# 51.net
KiCad netlist of a schematic drawn in Altium Designer
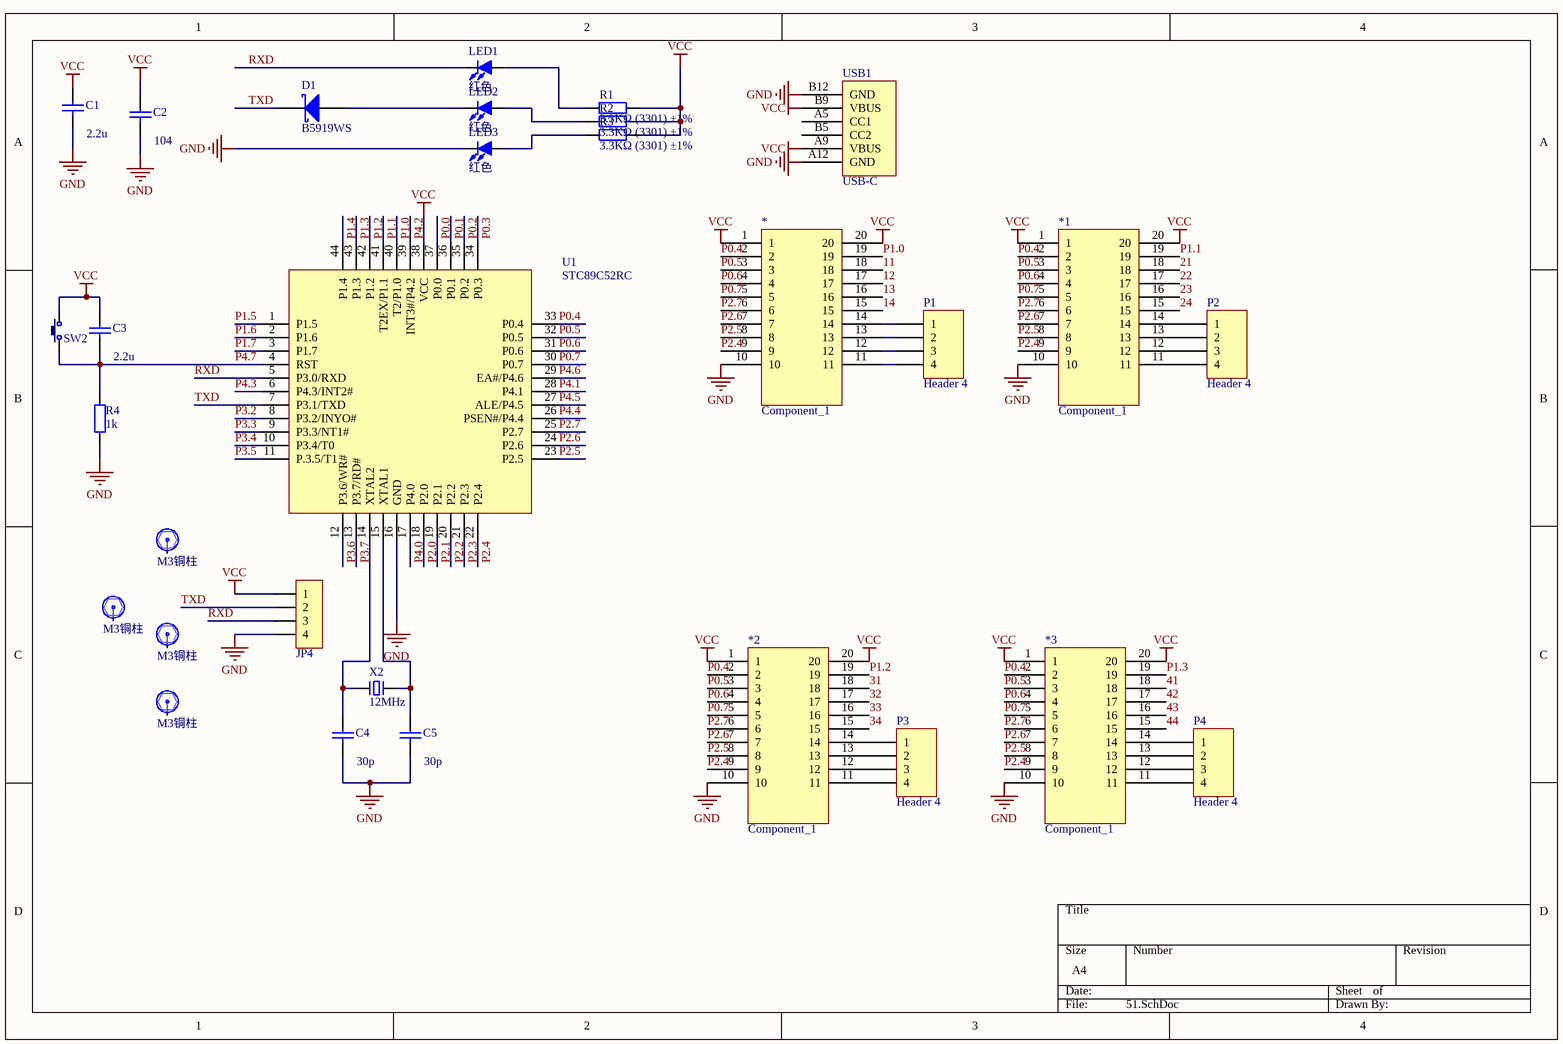
[diagram p0: 51.SchDoc]

(export (version "E")
  (design (tool "Eeschema 10.0.6"))
  (components
    (comp (ref "*")
      (value "Component_1")
      (footprint "SOP20_N")
      (libsource (lib "Schlib1") (part "Component_1"))
    )
    (comp (ref "*1")
      (value "Component_1")
      (footprint "SOP20_N")
      (libsource (lib "Schlib1") (part "Component_1"))
    )
    (comp (ref "*2")
      (value "Component_1")
      (footprint "SOP20_N")
      (libsource (lib "Schlib1") (part "Component_1"))
    )
    (comp (ref "*3")
      (value "Component_1")
      (footprint "SOP20_N")
      (libsource (lib "Schlib1") (part "Component_1"))
    )
    (comp (ref "C1")
      (value "2.2u")
      (footprint "0603_C")
      (description "贴片电容")
      (libsource (lib "Miscellaneous Devices LC") (part "0603 1uF (105) 10% 50V"))
    )
    (comp (ref "C2")
      (value "104")
      (footprint "0603_C")
      (description "贴片电容")
      (libsource (lib "Miscellaneous Devices LC") (part "0603 1uF (105) 10% 50V"))
    )
    (comp (ref "C3")
      (value "2.2u")
      (footprint "0603_C")
      (description "贴片电容")
      (libsource (lib "Miscellaneous Devices LC") (part "0603 1uF (105) 10% 50V"))
    )
    (comp (ref "C4")
      (value "30p")
      (footprint "0603_C")
      (description "贴片电容")
      (libsource (lib "Miscellaneous Devices LC") (part "0603 1uF (105) 10% 50V"))
    )
    (comp (ref "C5")
      (value "30p")
      (footprint "0603_C")
      (description "贴片电容")
      (libsource (lib "Miscellaneous Devices LC") (part "0603 1uF (105) 10% 50V"))
    )
    (comp (ref "D1")
      (value "B5919WS")
      (footprint "SMA")
      (description "肖特基二极管")
      (libsource (lib "0.2 - 二极管-整流桥") (part "1N5819"))
    )
    (comp (ref "JP4")
      (value "HDR-1X4")
      (footprint "HDR2.54-LI-4P")
      (description "4P接插件")
      (fields (field (name "版权归属") "封装库来自淘宝 ID：黄晶宝石"))
      (libsource (lib "5.4 - 接插件-脚距2.54 (100mil) ") (part "Header 4"))
    )
    (comp (ref "LED1")
      (value "红色")
      (footprint "LED 0603R")
      (description "贴片LED")
      (fields (field (name "版权归属") "封装库来自淘宝 ID：黄晶宝石"))
      (libsource (lib "0.3 - LED发光二极管") (part "LED-SMD"))
    )
    (comp (ref "LED2")
      (value "红色")
      (footprint "LED 0603R")
      (description "贴片LED")
      (fields (field (name "版权归属") "封装库来自淘宝 ID：黄晶宝石"))
      (libsource (lib "0.3 - LED发光二极管") (part "LED-SMD"))
    )
    (comp (ref "LED3")
      (value "红色")
      (footprint "LED 0603R")
      (description "贴片LED")
      (fields (field (name "版权归属") "封装库来自淘宝 ID：黄晶宝石"))
      (libsource (lib "0.3 - LED发光二极管") (part "LED-SMD"))
    )
    (comp (ref "P1")
      (value "Header 4")
      (footprint "HDR1X4")
      (description "Header, 4-Pin")
      (fields (field (name "PUBLISHER") "Altium Limited"))
      (libsource (lib "Miscellaneous Connectors") (part "Header 4"))
    )
    (comp (ref "P2")
      (value "Header 4")
      (footprint "HDR1X4")
      (description "Header, 4-Pin")
      (fields (field (name "PUBLISHER") "Altium Limited"))
      (libsource (lib "Miscellaneous Connectors") (part "Header 4"))
    )
    (comp (ref "P3")
      (value "Header 4")
      (footprint "HDR1X4")
      (description "Header, 4-Pin")
      (fields (field (name "PUBLISHER") "Altium Limited"))
      (libsource (lib "Miscellaneous Connectors") (part "Header 4"))
    )
    (comp (ref "P4")
      (value "Header 4")
      (footprint "HDR1X4")
      (description "Header, 4-Pin")
      (fields (field (name "PUBLISHER") "Altium Limited"))
      (libsource (lib "Miscellaneous Connectors") (part "Header 4"))
    )
    (comp (ref "R1")
      (value "3.3KΩ (3301) ±1%")
      (footprint "0805_R")
      (description "贴片电阻")
      (libsource (lib "") (part "0805 3.3KΩ (3301) 1%_1"))
    )
    (comp (ref "R2")
      (value "3.3KΩ (3301) ±1%")
      (footprint "0805_R")
      (description "贴片电阻")
      (libsource (lib "") (part "0805 3.3KΩ (3301) 1%_1"))
    )
    (comp (ref "R3")
      (value "3.3KΩ (3301) ±1%")
      (footprint "0805_R")
      (description "贴片电阻")
      (libsource (lib "") (part "0805 3.3KΩ (3301) 1%_1"))
    )
    (comp (ref "R4")
      (value "1k")
      (footprint "0805_R")
      (description "贴片电阻")
      (libsource (lib "Miscellaneous Devices LC") (part "0805 3.3KΩ (3301) 1%"))
    )
    (comp (ref "SW2")
      (value "3x6x5")
      (footprint "TSW DIP-3*6*5")
      (description "3x6轻触开关")
      (fields (field (name "版权归属") "封装库来自淘宝 ID：黄晶宝石"))
      (libsource (lib "0.7 - 常用按键-开关") (part "TSW 3x6"))
    )
    (comp (ref "U1")
      (value "STC89C52RC")
      (footprint "TQFP44 10x10_M")
      (description "STC单片机")
      (fields (field (name "版权归属") "源创客"))
      (libsource (lib "STC89C52RC贴片") (part "ATmega32U4"))
    )
    (comp (ref "USB1")
      (value "USB-C")
      (footprint "USB-C/S_C")
      (description "USB-C_6P型母接口")
      (libsource (lib "接口") (part "USB-C_6P/S"))
    )
    (comp (ref "X2")
      (value "12MHz")
      (footprint "OSC HC-49S")
      (description "2脚无源脚晶振")
      (fields (field (name "版权归属") "封装库来自淘宝卖家 ID：黄晶宝石"))
      (libsource (lib "2.0 - 保险丝-晶振-光耦") (part "XTAL-2P"))
    )
  )
  (nets
    (net (code "1") (name "/11") (class "Default")
      (node (ref "*") (pin "18") (pinfunction "18_18") (pintype "passive"))
    )
    (net (code "2") (name "/12") (class "Default")
      (node (ref "*") (pin "17") (pinfunction "17_17") (pintype "passive"))
    )
    (net (code "3") (name "/13") (class "Default")
      (node (ref "*") (pin "16") (pinfunction "16_16") (pintype "passive"))
    )
    (net (code "4") (name "/14") (class "Default")
      (node (ref "*") (pin "15") (pinfunction "15_15") (pintype "passive"))
    )
    (net (code "5") (name "/21") (class "Default")
      (node (ref "*1") (pin "18") (pinfunction "18_18") (pintype "passive"))
    )
    (net (code "6") (name "/22") (class "Default")
      (node (ref "*1") (pin "17") (pinfunction "17_17") (pintype "passive"))
    )
    (net (code "7") (name "/23") (class "Default")
      (node (ref "*1") (pin "16") (pinfunction "16_16") (pintype "passive"))
    )
    (net (code "8") (name "/24") (class "Default")
      (node (ref "*1") (pin "15") (pinfunction "15_15") (pintype "passive"))
    )
    (net (code "9") (name "/31") (class "Default")
      (node (ref "*2") (pin "18") (pinfunction "18_18") (pintype "passive"))
    )
    (net (code "10") (name "/32") (class "Default")
      (node (ref "*2") (pin "17") (pinfunction "17_17") (pintype "passive"))
    )
    (net (code "11") (name "/33") (class "Default")
      (node (ref "*2") (pin "16") (pinfunction "16_16") (pintype "passive"))
    )
    (net (code "12") (name "/34") (class "Default")
      (node (ref "*2") (pin "15") (pinfunction "15_15") (pintype "passive"))
    )
    (net (code "13") (name "/41") (class "Default")
      (node (ref "*3") (pin "18") (pinfunction "18_18") (pintype "passive"))
    )
    (net (code "14") (name "/42") (class "Default")
      (node (ref "*3") (pin "17") (pinfunction "17_17") (pintype "passive"))
    )
    (net (code "15") (name "/43") (class "Default")
      (node (ref "*3") (pin "16") (pinfunction "16_16") (pintype "passive"))
    )
    (net (code "16") (name "/44") (class "Default")
      (node (ref "*3") (pin "15") (pinfunction "15_15") (pintype "passive"))
    )
    (net (code "17") (name "/P0.0") (class "Default")
      (node (ref "U1") (pin "37") (pinfunction "P0.0_37") (pintype "passive"))
    )
    (net (code "18") (name "/P0.1") (class "Default")
      (node (ref "U1") (pin "36") (pinfunction "P0.1_36") (pintype "passive"))
    )
    (net (code "19") (name "/P0.2") (class "Default")
      (node (ref "U1") (pin "35") (pinfunction "P0.2_35") (pintype "passive"))
    )
    (net (code "20") (name "/P0.3") (class "Default")
      (node (ref "U1") (pin "34") (pinfunction "P0.3_34") (pintype "passive"))
    )
    (net (code "21") (name "/P0.4") (class "Default")
      (node (ref "*") (pin "2") (pinfunction "2_2") (pintype "passive"))
      (node (ref "*1") (pin "2") (pinfunction "2_2") (pintype "passive"))
      (node (ref "*2") (pin "2") (pinfunction "2_2") (pintype "passive"))
      (node (ref "*3") (pin "2") (pinfunction "2_2") (pintype "passive"))
      (node (ref "U1") (pin "33") (pinfunction "P0.4_33") (pintype "passive"))
    )
    (net (code "22") (name "/P0.5") (class "Default")
      (node (ref "*") (pin "3") (pinfunction "3_3") (pintype "passive"))
      (node (ref "*1") (pin "3") (pinfunction "3_3") (pintype "passive"))
      (node (ref "*2") (pin "3") (pinfunction "3_3") (pintype "passive"))
      (node (ref "*3") (pin "3") (pinfunction "3_3") (pintype "passive"))
      (node (ref "U1") (pin "32") (pinfunction "P0.5_32") (pintype "passive"))
    )
    (net (code "23") (name "/P0.6") (class "Default")
      (node (ref "*") (pin "4") (pinfunction "4_4") (pintype "passive"))
      (node (ref "*1") (pin "4") (pinfunction "4_4") (pintype "passive"))
      (node (ref "*2") (pin "4") (pinfunction "4_4") (pintype "passive"))
      (node (ref "*3") (pin "4") (pinfunction "4_4") (pintype "passive"))
      (node (ref "U1") (pin "31") (pinfunction "P0.6_31") (pintype "passive"))
    )
    (net (code "24") (name "/P0.7") (class "Default")
      (node (ref "*") (pin "5") (pinfunction "5_5") (pintype "passive"))
      (node (ref "*1") (pin "5") (pinfunction "5_5") (pintype "passive"))
      (node (ref "*2") (pin "5") (pinfunction "5_5") (pintype "passive"))
      (node (ref "*3") (pin "5") (pinfunction "5_5") (pintype "passive"))
      (node (ref "U1") (pin "30") (pinfunction "P0.7_30") (pintype "passive"))
    )
    (net (code "25") (name "/P1.0") (class "Default")
      (node (ref "*") (pin "19") (pinfunction "19_19") (pintype "passive"))
      (node (ref "U1") (pin "40") (pinfunction "T2/P1.0_40") (pintype "passive"))
    )
    (net (code "26") (name "/P1.1") (class "Default")
      (node (ref "*1") (pin "19") (pinfunction "19_19") (pintype "passive"))
      (node (ref "U1") (pin "41") (pinfunction "T2EX/P1.1_41") (pintype "passive"))
    )
    (net (code "27") (name "/P1.2") (class "Default")
      (node (ref "*2") (pin "19") (pinfunction "19_19") (pintype "passive"))
      (node (ref "U1") (pin "42") (pinfunction "P1.2_42") (pintype "passive"))
    )
    (net (code "28") (name "/P1.3") (class "Default")
      (node (ref "*3") (pin "19") (pinfunction "19_19") (pintype "passive"))
      (node (ref "U1") (pin "43") (pinfunction "P1.3_43") (pintype "passive"))
    )
    (net (code "29") (name "/P1.4") (class "Default")
      (node (ref "U1") (pin "44") (pinfunction "P1.4_44") (pintype "passive"))
    )
    (net (code "30") (name "/P1.5") (class "Default")
      (node (ref "U1") (pin "1") (pinfunction "P1.5_1") (pintype "passive"))
    )
    (net (code "31") (name "/P1.6") (class "Default")
      (node (ref "U1") (pin "2") (pinfunction "P1.6_2") (pintype "passive"))
    )
    (net (code "32") (name "/P1.7") (class "Default")
      (node (ref "U1") (pin "3") (pinfunction "P1.7_3") (pintype "passive"))
    )
    (net (code "33") (name "/P2.0") (class "Default")
      (node (ref "U1") (pin "18") (pinfunction "P2.0_18") (pintype "passive"))
    )
    (net (code "34") (name "/P2.1") (class "Default")
      (node (ref "U1") (pin "19") (pinfunction "P2.1_19") (pintype "passive"))
    )
    (net (code "35") (name "/P2.2") (class "Default")
      (node (ref "U1") (pin "20") (pinfunction "P2.2_20") (pintype "passive"))
    )
    (net (code "36") (name "/P2.3") (class "Default")
      (node (ref "U1") (pin "21") (pinfunction "P2.3_21") (pintype "passive"))
    )
    (net (code "37") (name "/P2.4") (class "Default")
      (node (ref "*") (pin "9") (pinfunction "9_9") (pintype "passive"))
      (node (ref "*1") (pin "9") (pinfunction "9_9") (pintype "passive"))
      (node (ref "*2") (pin "9") (pinfunction "9_9") (pintype "passive"))
      (node (ref "*3") (pin "9") (pinfunction "9_9") (pintype "passive"))
      (node (ref "U1") (pin "22") (pinfunction "P2.4_22") (pintype "passive"))
    )
    (net (code "38") (name "/P2.5") (class "Default")
      (node (ref "*") (pin "8") (pinfunction "8_8") (pintype "passive"))
      (node (ref "*1") (pin "8") (pinfunction "8_8") (pintype "passive"))
      (node (ref "*2") (pin "8") (pinfunction "8_8") (pintype "passive"))
      (node (ref "*3") (pin "8") (pinfunction "8_8") (pintype "passive"))
      (node (ref "U1") (pin "23") (pinfunction "P2.5_23") (pintype "passive"))
    )
    (net (code "39") (name "/P2.6") (class "Default")
      (node (ref "*") (pin "7") (pinfunction "7_7") (pintype "passive"))
      (node (ref "*1") (pin "7") (pinfunction "7_7") (pintype "passive"))
      (node (ref "*2") (pin "7") (pinfunction "7_7") (pintype "passive"))
      (node (ref "*3") (pin "7") (pinfunction "7_7") (pintype "passive"))
      (node (ref "U1") (pin "24") (pinfunction "P2.6_24") (pintype "passive"))
    )
    (net (code "40") (name "/P2.7") (class "Default")
      (node (ref "*") (pin "6") (pinfunction "6_6") (pintype "passive"))
      (node (ref "*1") (pin "6") (pinfunction "6_6") (pintype "passive"))
      (node (ref "*2") (pin "6") (pinfunction "6_6") (pintype "passive"))
      (node (ref "*3") (pin "6") (pinfunction "6_6") (pintype "passive"))
      (node (ref "U1") (pin "25") (pinfunction "P2.7_25") (pintype "passive"))
    )
    (net (code "41") (name "/P3.2") (class "Default")
      (node (ref "U1") (pin "8") (pinfunction "P3.2/INYO#_8") (pintype "passive"))
    )
    (net (code "42") (name "/P3.3") (class "Default")
      (node (ref "U1") (pin "9") (pinfunction "P3.3/NT1#_9") (pintype "passive"))
    )
    (net (code "43") (name "/P3.4") (class "Default")
      (node (ref "U1") (pin "10") (pinfunction "P3.4/T0_10") (pintype "passive"))
    )
    (net (code "44") (name "/P3.5") (class "Default")
      (node (ref "U1") (pin "11") (pinfunction "P.3.5/T1_11") (pintype "passive"))
    )
    (net (code "45") (name "/P3.6") (class "Default")
      (node (ref "U1") (pin "12") (pinfunction "P3.6/WR#_12") (pintype "passive"))
    )
    (net (code "46") (name "/P3.7") (class "Default")
      (node (ref "U1") (pin "13") (pinfunction "P3.7/RD#_13") (pintype "passive"))
    )
    (net (code "47") (name "/P4.0") (class "Default")
      (node (ref "U1") (pin "17") (pinfunction "P4.0_17") (pintype "passive"))
    )
    (net (code "48") (name "/P4.1") (class "Default")
      (node (ref "U1") (pin "28") (pinfunction "P4.1_28") (pintype "passive"))
    )
    (net (code "49") (name "/P4.2") (class "Default")
      (node (ref "U1") (pin "39") (pinfunction "INT3#/P4.2_39") (pintype "passive"))
    )
    (net (code "50") (name "/P4.3") (class "Default")
      (node (ref "U1") (pin "6") (pinfunction "P4.3/INT2#_6") (pintype "passive"))
    )
    (net (code "51") (name "/P4.4") (class "Default")
      (node (ref "U1") (pin "26") (pinfunction "PSEN#/P4.4_26") (pintype "passive"))
    )
    (net (code "52") (name "/P4.5") (class "Default")
      (node (ref "U1") (pin "27") (pinfunction "ALE/P4.5_27") (pintype "passive"))
    )
    (net (code "53") (name "/P4.6") (class "Default")
      (node (ref "U1") (pin "29") (pinfunction "EA#/P4.6_29") (pintype "passive"))
    )
    (net (code "54") (name "/P4.7") (class "Default")
      (node (ref "C3") (pin "1") (pinfunction "1_1") (pintype "passive"))
      (node (ref "R4") (pin "2") (pinfunction "2_2") (pintype "passive"))
      (node (ref "SW2") (pin "1") (pinfunction "1_1") (pintype "passive"))
      (node (ref "U1") (pin "4") (pinfunction "RST_4") (pintype "passive"))
    )
    (net (code "55") (name "/RXD") (class "Default")
      (node (ref "JP4") (pin "3") (pinfunction "3_3") (pintype "passive"))
      (node (ref "LED1") (pin "2") (pinfunction "K_2") (pintype "passive"))
      (node (ref "U1") (pin "5") (pinfunction "P3.0/RXD_5") (pintype "passive"))
    )
    (net (code "56") (name "/TXD") (class "Default")
      (node (ref "D1") (pin "2") (pinfunction "K_2") (pintype "passive"))
      (node (ref "JP4") (pin "2") (pinfunction "2_2") (pintype "passive"))
      (node (ref "U1") (pin "7") (pinfunction "P3.1/TXD_7") (pintype "passive"))
    )
    (net (code "57") (name "GND") (class "Default")
      (node (ref "*") (pin "10") (pinfunction "10_10") (pintype "passive"))
      (node (ref "*1") (pin "10") (pinfunction "10_10") (pintype "passive"))
      (node (ref "*2") (pin "10") (pinfunction "10_10") (pintype "passive"))
      (node (ref "*3") (pin "10") (pinfunction "10_10") (pintype "passive"))
      (node (ref "C1") (pin "1") (pinfunction "1_1") (pintype "passive"))
      (node (ref "C2") (pin "1") (pinfunction "1_1") (pintype "passive"))
      (node (ref "C4") (pin "1") (pinfunction "1_1") (pintype "passive"))
      (node (ref "C5") (pin "1") (pinfunction "1_1") (pintype "passive"))
      (node (ref "JP4") (pin "4") (pinfunction "4_4") (pintype "passive"))
      (node (ref "LED3") (pin "2") (pinfunction "K_2") (pintype "passive"))
      (node (ref "R4") (pin "1") (pinfunction "1_1") (pintype "passive"))
      (node (ref "U1") (pin "16") (pinfunction "GND_16") (pintype "passive"))
      (node (ref "USB1") (pin "A12") (pinfunction "GND_A12") (pintype "passive"))
      (node (ref "USB1") (pin "B12") (pinfunction "GND_B12") (pintype "passive"))
    )
    (net (code "58") (name "Net-(*-Pad11)") (class "Default")
      (node (ref "*") (pin "11") (pinfunction "11_11") (pintype "passive"))
      (node (ref "P1") (pin "4") (pinfunction "4_4") (pintype "passive"))
    )
    (net (code "59") (name "Net-(*-Pad12)") (class "Default")
      (node (ref "*") (pin "12") (pinfunction "12_12") (pintype "passive"))
      (node (ref "P1") (pin "3") (pinfunction "3_3") (pintype "passive"))
    )
    (net (code "60") (name "Net-(*-Pad13)") (class "Default")
      (node (ref "*") (pin "13") (pinfunction "13_13") (pintype "passive"))
      (node (ref "P1") (pin "2") (pinfunction "2_2") (pintype "passive"))
    )
    (net (code "61") (name "Net-(*-Pad14)") (class "Default")
      (node (ref "*") (pin "14") (pinfunction "14_14") (pintype "passive"))
      (node (ref "P1") (pin "1") (pinfunction "1_1") (pintype "passive"))
    )
    (net (code "62") (name "Net-(*1-Pad11)") (class "Default")
      (node (ref "*1") (pin "11") (pinfunction "11_11") (pintype "passive"))
      (node (ref "P2") (pin "4") (pinfunction "4_4") (pintype "passive"))
    )
    (net (code "63") (name "Net-(*1-Pad12)") (class "Default")
      (node (ref "*1") (pin "12") (pinfunction "12_12") (pintype "passive"))
      (node (ref "P2") (pin "3") (pinfunction "3_3") (pintype "passive"))
    )
    (net (code "64") (name "Net-(*1-Pad13)") (class "Default")
      (node (ref "*1") (pin "13") (pinfunction "13_13") (pintype "passive"))
      (node (ref "P2") (pin "2") (pinfunction "2_2") (pintype "passive"))
    )
    (net (code "65") (name "Net-(*1-Pad14)") (class "Default")
      (node (ref "*1") (pin "14") (pinfunction "14_14") (pintype "passive"))
      (node (ref "P2") (pin "1") (pinfunction "1_1") (pintype "passive"))
    )
    (net (code "66") (name "Net-(*2-Pad11)") (class "Default")
      (node (ref "*2") (pin "11") (pinfunction "11_11") (pintype "passive"))
      (node (ref "P3") (pin "4") (pinfunction "4_4") (pintype "passive"))
    )
    (net (code "67") (name "Net-(*2-Pad12)") (class "Default")
      (node (ref "*2") (pin "12") (pinfunction "12_12") (pintype "passive"))
      (node (ref "P3") (pin "3") (pinfunction "3_3") (pintype "passive"))
    )
    (net (code "68") (name "Net-(*2-Pad13)") (class "Default")
      (node (ref "*2") (pin "13") (pinfunction "13_13") (pintype "passive"))
      (node (ref "P3") (pin "2") (pinfunction "2_2") (pintype "passive"))
    )
    (net (code "69") (name "Net-(*2-Pad14)") (class "Default")
      (node (ref "*2") (pin "14") (pinfunction "14_14") (pintype "passive"))
      (node (ref "P3") (pin "1") (pinfunction "1_1") (pintype "passive"))
    )
    (net (code "70") (name "Net-(*3-Pad11)") (class "Default")
      (node (ref "*3") (pin "11") (pinfunction "11_11") (pintype "passive"))
      (node (ref "P4") (pin "4") (pinfunction "4_4") (pintype "passive"))
    )
    (net (code "71") (name "Net-(*3-Pad12)") (class "Default")
      (node (ref "*3") (pin "12") (pinfunction "12_12") (pintype "passive"))
      (node (ref "P4") (pin "3") (pinfunction "3_3") (pintype "passive"))
    )
    (net (code "72") (name "Net-(*3-Pad13)") (class "Default")
      (node (ref "*3") (pin "13") (pinfunction "13_13") (pintype "passive"))
      (node (ref "P4") (pin "2") (pinfunction "2_2") (pintype "passive"))
    )
    (net (code "73") (name "Net-(*3-Pad14)") (class "Default")
      (node (ref "*3") (pin "14") (pinfunction "14_14") (pintype "passive"))
      (node (ref "P4") (pin "1") (pinfunction "1_1") (pintype "passive"))
    )
    (net (code "74") (name "Net-(D1-A)") (class "Default")
      (node (ref "D1") (pin "1") (pinfunction "A_1") (pintype "passive"))
      (node (ref "LED2") (pin "2") (pinfunction "K_2") (pintype "passive"))
    )
    (net (code "75") (name "Net-(LED1-A)") (class "Default")
      (node (ref "LED1") (pin "1") (pinfunction "A_1") (pintype "passive"))
      (node (ref "R1") (pin "1") (pinfunction "1_1") (pintype "passive"))
    )
    (net (code "76") (name "Net-(LED2-A)") (class "Default")
      (node (ref "LED2") (pin "1") (pinfunction "A_1") (pintype "passive"))
      (node (ref "R2") (pin "1") (pinfunction "1_1") (pintype "passive"))
    )
    (net (code "77") (name "Net-(LED3-A)") (class "Default")
      (node (ref "LED3") (pin "1") (pinfunction "A_1") (pintype "passive"))
      (node (ref "R3") (pin "1") (pinfunction "1_1") (pintype "passive"))
    )
    (net (code "78") (name "Net-(U1-XTAL1)") (class "Default")
      (node (ref "C5") (pin "2") (pinfunction "2_2") (pintype "passive"))
      (node (ref "U1") (pin "15") (pinfunction "XTAL1_15") (pintype "passive"))
      (node (ref "X2") (pin "2") (pinfunction "2_2") (pintype "passive"))
    )
    (net (code "79") (name "Net-(U1-XTAL2)") (class "Default")
      (node (ref "C4") (pin "2") (pinfunction "2_2") (pintype "passive"))
      (node (ref "U1") (pin "14") (pinfunction "XTAL2_14") (pintype "passive"))
      (node (ref "X2") (pin "1") (pinfunction "1_1") (pintype "passive"))
    )
    (net (code "80") (name "VCC") (class "Default")
      (node (ref "*") (pin "1") (pinfunction "1_1") (pintype "passive"))
      (node (ref "*") (pin "20") (pinfunction "20_20") (pintype "passive"))
      (node (ref "*1") (pin "1") (pinfunction "1_1") (pintype "passive"))
      (node (ref "*1") (pin "20") (pinfunction "20_20") (pintype "passive"))
      (node (ref "*2") (pin "1") (pinfunction "1_1") (pintype "passive"))
      (node (ref "*2") (pin "20") (pinfunction "20_20") (pintype "passive"))
      (node (ref "*3") (pin "1") (pinfunction "1_1") (pintype "passive"))
      (node (ref "*3") (pin "20") (pinfunction "20_20") (pintype "passive"))
      (node (ref "C1") (pin "2") (pinfunction "2_2") (pintype "passive"))
      (node (ref "C2") (pin "2") (pinfunction "2_2") (pintype "passive"))
      (node (ref "C3") (pin "2") (pinfunction "2_2") (pintype "passive"))
      (node (ref "JP4") (pin "1") (pinfunction "1_1") (pintype "passive"))
      (node (ref "R1") (pin "2") (pinfunction "2_2") (pintype "passive"))
      (node (ref "R2") (pin "2") (pinfunction "2_2") (pintype "passive"))
      (node (ref "R3") (pin "2") (pinfunction "2_2") (pintype "passive"))
      (node (ref "SW2") (pin "2") (pinfunction "2_2") (pintype "passive"))
      (node (ref "U1") (pin "38") (pinfunction "VCC_38") (pintype "passive"))
      (node (ref "USB1") (pin "A9") (pinfunction "VBUS_A9") (pintype "passive"))
      (node (ref "USB1") (pin "B9") (pinfunction "VBUS_B9") (pintype "passive"))
    )
    (net (code "85") (name "unconnected-(USB1-CC1-PadA5)") (class "Default")
      (node (ref "USB1") (pin "A5") (pinfunction "CC1_A5") (pintype "passive"))
    )
    (net (code "86") (name "unconnected-(USB1-CC2-PadB5)") (class "Default")
      (node (ref "USB1") (pin "B5") (pinfunction "CC2_B5") (pintype "passive"))
    )
  )
)
